# Copy_of_3_3V_Buck.net
KiCad netlist of a schematic drawn in Altium Designer
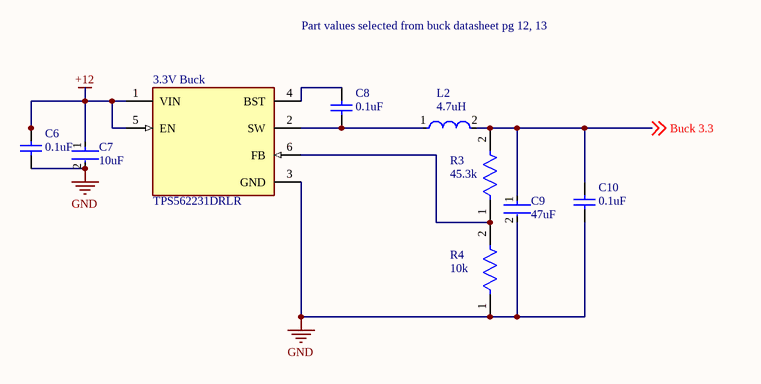
[diagram p0: Copy of 3.3V Buck.SchDoc]

(export (version "E")
  (design (tool "Eeschema 10.0.6"))
  (components
    (comp (ref "3.3V Buck")
      (value "TPS562231DRLR")
      (footprint "FP-DRL0006A-MFG")
      (description "POWER MANAGEMENT")
      (libsource (lib "Altium Content Vault") (part "11aae5693f510e0d396f49b7d198f22"))
    )
    (comp (ref "C6")
      (value "0.1uF")
      (footprint "CAPC2013X94X50LL20T25")
      (fields
        (field (name "PART NUMBER") "08055C104JAT4A")
        (field (name "MANUFACTURER") "AVX Interconnect / Elco")
      )
      (libsource (lib "Altium Content Vault") (part "CAP"))
    )
    (comp (ref "C7")
      (value "10uF")
      (footprint "FP-CL21-IPC_B")
      (description "CL21 Series 0805 10uF 25V ±10% Tolerance X5R Multilayer Ceramic Chip Capacitor")
      (fields (field (name "TOLERANCE") "10%"))
      (libsource (lib "Altium Content Vault") (part "b4654b650e69147ec39a6b967a45e02"))
    )
    (comp (ref "C8")
      (value "0.1uF")
      (footprint "CAPC2013X94X50LL20T25")
      (fields
        (field (name "PART NUMBER") "08055C104JAT4A")
        (field (name "MANUFACTURER") "AVX Interconnect / Elco")
      )
      (libsource (lib "Altium Content Vault") (part "CAP"))
    )
    (comp (ref "C9")
      (value "47uF")
      (footprint "FP-C3216-160-0_2-MFG")
      (description "Multilayer Ceramic Capacitors 47uF ±20% 25V X5R SMD 1206")
      (fields (field (name "VOLTAGE") "25V") (field (name "TOLERANCE") "20%"))
      (libsource (lib "Altium Content Vault") (part "11868f565c42a9108669ba33697ecf6"))
    )
    (comp (ref "C10")
      (value "0.1uF")
      (footprint "CAPC2013X94X50LL20T25")
      (fields
        (field (name "PART NUMBER") "08055C104JAT4A")
        (field (name "MANUFACTURER") "AVX Interconnect / Elco")
      )
      (libsource (lib "Altium Content Vault") (part "CAP"))
    )
    (comp (ref "L2")
      (value "4.7uH")
      (footprint "FP-NR8040-H_4_2-MFG")
      (description "Shielded Wirewound Inductor 4.7uH 30% 4.1A 23.4mΩ SMD")
      (fields (field (name "TOLERANCE") "30%"))
      (libsource (lib "Altium Content Vault") (part "725321dda6339637d4d059423bc1c3c"))
    )
    (comp (ref "R3")
      (value "45.3k")
      (footprint "FP-RT0603-MFG")
      (description "RES SMD 45.3K OHM 1% 1/10W 0603")
      (fields
        (field (name "TOLERANCE") "0.01")
        (field (name "OCTOPART") "https://octopart.com/rt0603fre0745k3l-yageo-1367333")
      )
      (libsource (lib "Altium Content Vault") (part "1029c3af85768c4190bb7ad29bc67b5"))
    )
    (comp (ref "R4")
      (value "10k")
      (footprint "FP-RK73H1J-IPC_B")
      (description "10kΩ ±1% 0.1W Chip Resistor 0603 Thick Film AEC-Q200 Qualified")
      (fields (field (name "TOLERANCE") "1%"))
      (libsource (lib "Altium Content Vault") (part "1029c3af85768c4190bb7ad29bc67b5"))
    )
  )
  (nets
    (net (code "1") (name "+12") (class "Default")
      (node (ref "3.3V Buck") (pin "1") (pinfunction "VIN_1") (pintype "power_in"))
      (node (ref "3.3V Buck") (pin "5") (pinfunction "EN_5") (pintype "input"))
      (node (ref "C6") (pin "2") (pinfunction "2_2") (pintype "passive"))
      (node (ref "C7") (pin "1") (pinfunction "1_1") (pintype "passive"))
    )
    (net (code "2") (name "Buck 3.3") (class "Default")
      (node (ref "C10") (pin "2") (pinfunction "2_2") (pintype "passive"))
      (node (ref "C9") (pin "1") (pinfunction "1_1") (pintype "passive"))
      (node (ref "L2") (pin "2") (pinfunction "2_2") (pintype "passive"))
      (node (ref "R3") (pin "2") (pinfunction "2_2") (pintype "passive"))
    )
    (net (code "3") (name "GND") (class "Default")
      (node (ref "3.3V Buck") (pin "3") (pinfunction "GND_3") (pintype "power_in"))
      (node (ref "C10") (pin "1") (pinfunction "1_1") (pintype "passive"))
      (node (ref "C6") (pin "1") (pinfunction "1_1") (pintype "passive"))
      (node (ref "C7") (pin "2") (pinfunction "2_2") (pintype "passive"))
      (node (ref "C9") (pin "2") (pinfunction "2_2") (pintype "passive"))
      (node (ref "R4") (pin "1") (pinfunction "1_1") (pintype "passive"))
    )
    (net (code "4") (name "Net-(3.3V Buck-BST)") (class "Default")
      (node (ref "3.3V Buck") (pin "4") (pinfunction "BST_4") (pintype "passive"))
      (node (ref "C8") (pin "2") (pinfunction "2_2") (pintype "passive"))
    )
    (net (code "5") (name "Net-(3.3V Buck-FB)") (class "Default")
      (node (ref "3.3V Buck") (pin "6") (pinfunction "FB_6") (pintype "input"))
      (node (ref "R3") (pin "1") (pinfunction "1_1") (pintype "passive"))
      (node (ref "R4") (pin "2") (pinfunction "2_2") (pintype "passive"))
    )
    (net (code "6") (name "Net-(3.3V Buck-SW)") (class "Default")
      (node (ref "3.3V Buck") (pin "2") (pinfunction "SW_2") (pintype "passive"))
      (node (ref "C8") (pin "1") (pinfunction "1_1") (pintype "passive"))
      (node (ref "L2") (pin "1") (pinfunction "1_1") (pintype "passive"))
    )
  )
)
